# Module_T_H_04vP.net
KiCad netlist of a schematic drawn in EAGLE
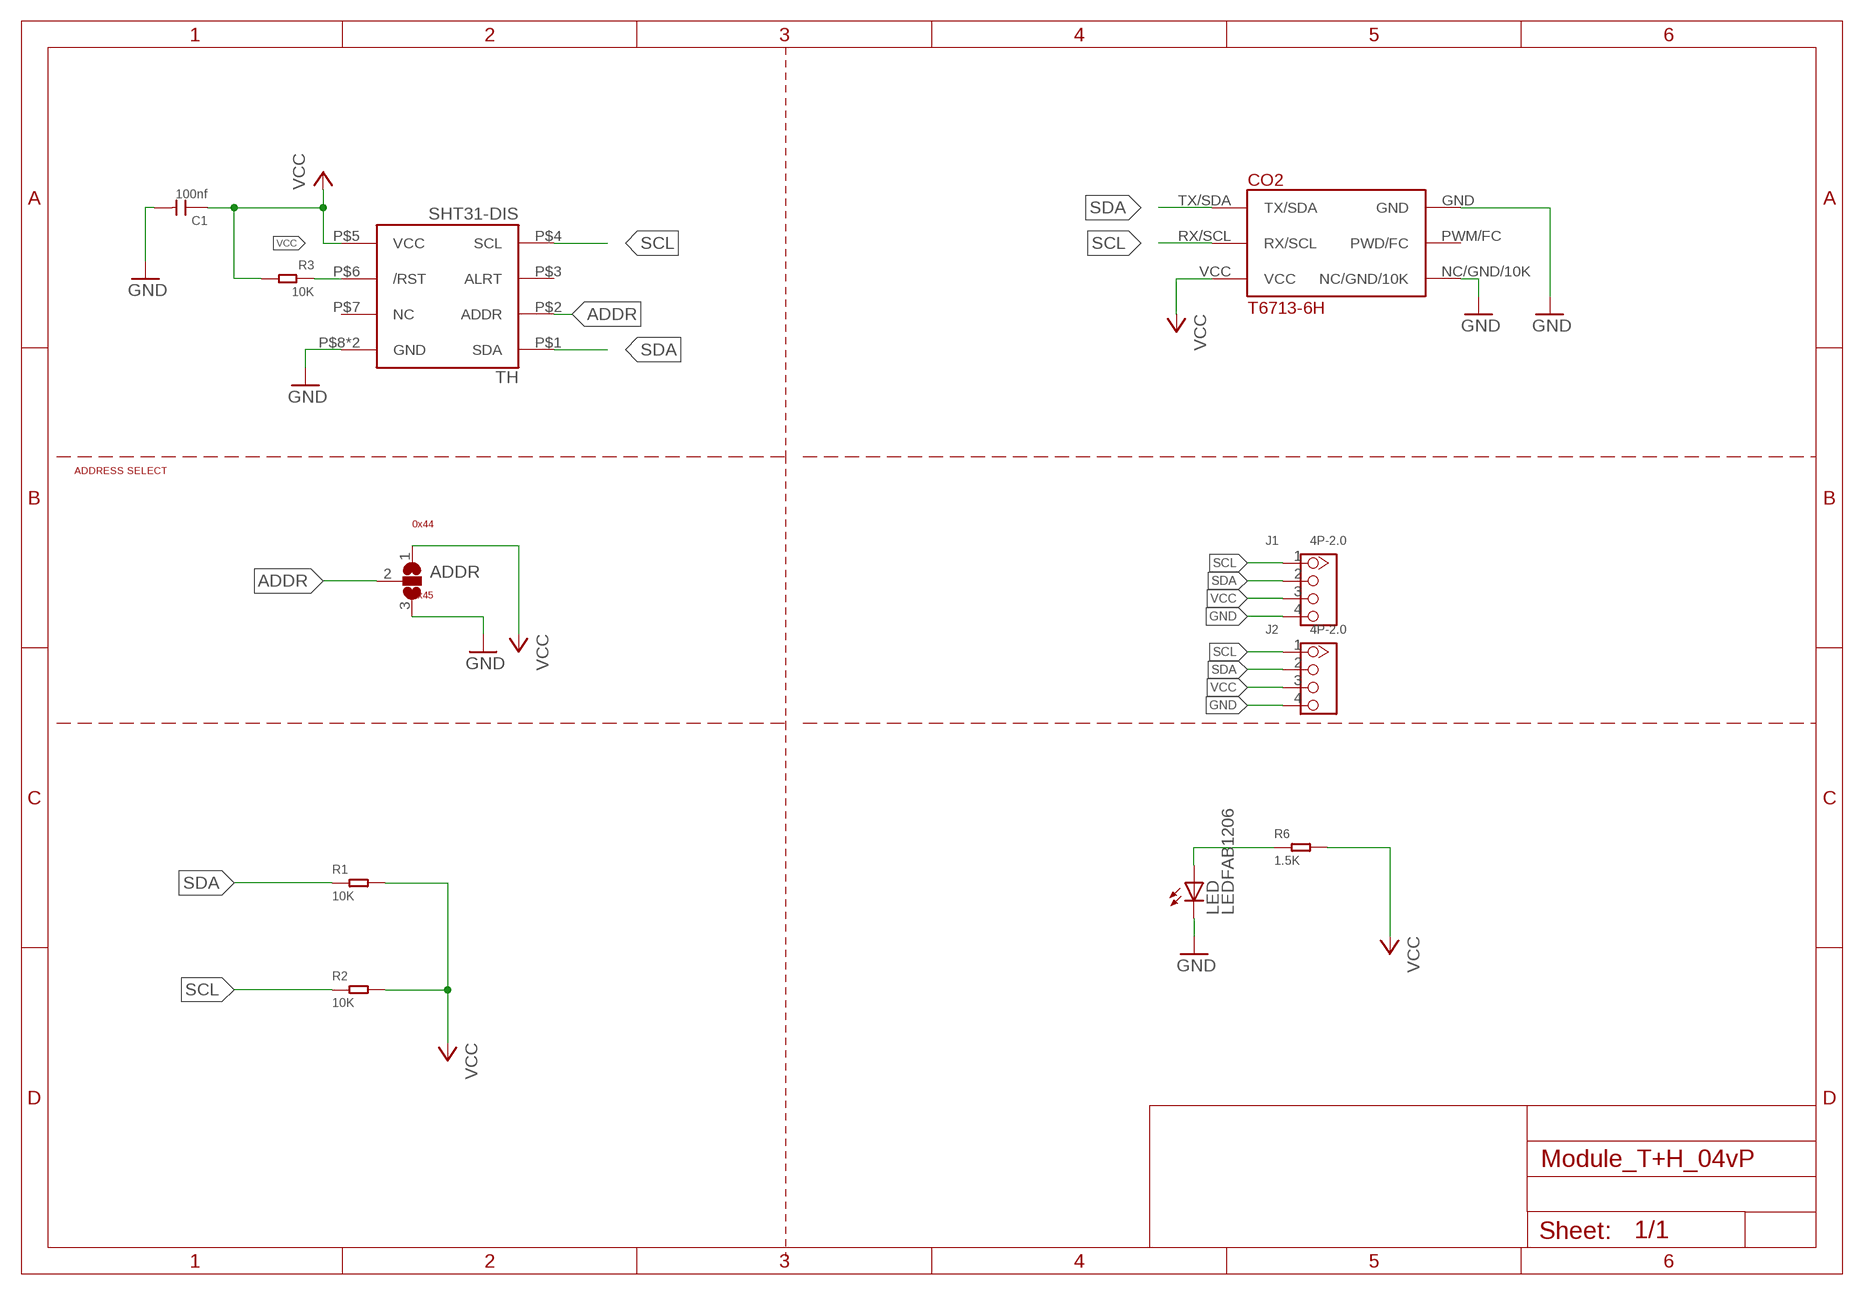
[diagram p0: schematic, sheet 1]

(export (version "E")
  (design (tool "Eeschema 10.0.6"))
  (components
    (comp (ref "ADDR")
      (value "SJ2W")
      (footprint "eagle-import:SJ_2")
      (libsource (lib "eagle-import") (part "SJ2W"))
    )
    (comp (ref "C1")
      (value "100nf")
      (footprint "eagle-import:C0805")
      (fields (field (name "MPN") "CC0805KRX7R9BB104"))
      (libsource (lib "eagle-import") (part "CERAMIC-100NF-50V-10%-X7R(0805)"))
    )
    (comp (ref "CO2")
      (value "T6713-6H")
      (footprint "eagle-import:PINS")
      (libsource (lib "eagle-import") (part "T6713-6H"))
    )
    (comp (ref "J1")
      (value "4P-2.0")
      (footprint "eagle-import:HW4-2.0")
      (libsource (lib "eagle-import") (part "GROVE-CONNECTOR-DIP(4P-2.0)"))
    )
    (comp (ref "J2")
      (value "4P-2.0")
      (footprint "eagle-import:HW4-2.0")
      (libsource (lib "eagle-import") (part "GROVE-CONNECTOR-DIP(4P-2.0)"))
    )
    (comp (ref "LED")
      (value "LEDFAB1206")
      (footprint "eagle-import:LED1206FAB")
      (libsource (lib "eagle-import") (part "LEDFAB1206"))
    )
    (comp (ref "R1")
      (value "10K")
      (footprint "eagle-import:R0805")
      (fields (field (name "MPN") "RC0805FR-0710KL"))
      (libsource (lib "eagle-import") (part "SMD-RES-10K-1%-1/8W(0805)"))
    )
    (comp (ref "R2")
      (value "10K")
      (footprint "eagle-import:R0805")
      (fields (field (name "MPN") "RC0805FR-0710KL"))
      (libsource (lib "eagle-import") (part "SMD-RES-10K-1%-1/8W(0805)"))
    )
    (comp (ref "R3")
      (value "10K")
      (footprint "eagle-import:R0805")
      (fields (field (name "MPN") "RC0805FR-0710KL"))
      (libsource (lib "eagle-import") (part "SMD-RES-10K-1%-1/8W(0805)"))
    )
    (comp (ref "R6")
      (value "1.5K")
      (footprint "eagle-import:R0805")
      (fields (field (name "MPN") "RC0805FR-071K5L"))
      (libsource (lib "eagle-import") (part "SMD-RES-1.5K-1%-1/8W(0805)"))
    )
    (comp (ref "TH")
      (value "SHT31-DIS")
      (footprint "eagle-import:SHT3X")
      (libsource (lib "eagle-import") (part "SHT31-DIS"))
    )
  )
  (nets
    (net (code "1") (name "ADDR") (class "Default")
      (node (ref "ADDR") (pin "2") (pinfunction "2_2") (pintype "passive"))
      (node (ref "TH") (pin "P$2") (pinfunction "ADDR_P$2") (pintype "bidirectional"))
    )
    (net (code "2") (name "GND") (class "Default")
      (node (ref "ADDR") (pin "3") (pinfunction "3_3") (pintype "passive"))
      (node (ref "C1") (pin "2") (pinfunction "2_2") (pintype "passive"))
      (node (ref "CO2") (pin "GND") (pinfunction "GND_GND") (pintype "bidirectional"))
      (node (ref "CO2") (pin "NC/GND/10K") (pinfunction "NC/GND/10K_NC/GND/10K") (pintype "bidirectional"))
      (node (ref "J1") (pin "4") (pinfunction "4_4") (pintype "bidirectional"))
      (node (ref "J2") (pin "4") (pinfunction "4_4") (pintype "bidirectional"))
      (node (ref "LED") (pin "2") (pinfunction "C_2") (pintype "passive"))
      (node (ref "TH") (pin "P$8") (pinfunction "GND_P$8") (pintype "bidirectional"))
      (node (ref "TH") (pin "PAD") (pinfunction "GND_PAD") (pintype "bidirectional"))
    )
    (net (code "3") (name "Net-(LED-A)") (class "Default")
      (node (ref "LED") (pin "1") (pinfunction "A_1") (pintype "passive"))
      (node (ref "R6") (pin "1") (pinfunction "1_1") (pintype "passive"))
    )
    (net (code "4") (name "Net-(TH-{slash}RST)") (class "Default")
      (node (ref "R3") (pin "1") (pinfunction "1_1") (pintype "passive"))
      (node (ref "TH") (pin "P$6") (pinfunction "/RST_P$6") (pintype "bidirectional"))
    )
    (net (code "5") (name "SCL") (class "Default")
      (node (ref "CO2") (pin "RX/SCL") (pinfunction "RX/SCL_RX/SCL") (pintype "bidirectional"))
      (node (ref "J1") (pin "1") (pinfunction "1_1") (pintype "bidirectional"))
      (node (ref "J2") (pin "1") (pinfunction "1_1") (pintype "bidirectional"))
      (node (ref "R2") (pin "1") (pinfunction "1_1") (pintype "passive"))
      (node (ref "TH") (pin "P$4") (pinfunction "SCL_P$4") (pintype "bidirectional"))
    )
    (net (code "6") (name "SDA") (class "Default")
      (node (ref "CO2") (pin "TX/SDA") (pinfunction "TX/SDA_TX/SDA") (pintype "bidirectional"))
      (node (ref "J1") (pin "2") (pinfunction "2_2") (pintype "bidirectional"))
      (node (ref "J2") (pin "2") (pinfunction "2_2") (pintype "bidirectional"))
      (node (ref "R1") (pin "1") (pinfunction "1_1") (pintype "passive"))
      (node (ref "TH") (pin "P$1") (pinfunction "SDA_P$1") (pintype "bidirectional"))
    )
    (net (code "7") (name "VCC") (class "Default")
      (node (ref "ADDR") (pin "1") (pinfunction "1_1") (pintype "passive"))
      (node (ref "C1") (pin "1") (pinfunction "1_1") (pintype "passive"))
      (node (ref "CO2") (pin "VCC") (pinfunction "VCC_VCC") (pintype "bidirectional"))
      (node (ref "J1") (pin "3") (pinfunction "3_3") (pintype "bidirectional"))
      (node (ref "J2") (pin "3") (pinfunction "3_3") (pintype "bidirectional"))
      (node (ref "R1") (pin "2") (pinfunction "2_2") (pintype "passive"))
      (node (ref "R2") (pin "2") (pinfunction "2_2") (pintype "passive"))
      (node (ref "R3") (pin "2") (pinfunction "2_2") (pintype "passive"))
      (node (ref "R6") (pin "2") (pinfunction "2_2") (pintype "passive"))
      (node (ref "TH") (pin "P$5") (pinfunction "VCC_P$5") (pintype "bidirectional"))
    )
    (net (code "8") (name "unconnected-(CO2-PWD{slash}FC-PadPWM{slash}FC)") (class "Default")
      (node (ref "CO2") (pin "PWM/FC") (pinfunction "PWD/FC_PWM/FC") (pintype "bidirectional"))
    )
    (net (code "9") (name "unconnected-(TH-ALRT-PadP$3)") (class "Default")
      (node (ref "TH") (pin "P$3") (pinfunction "ALRT_P$3") (pintype "bidirectional"))
    )
    (net (code "10") (name "unconnected-(TH-NC-PadP$7)") (class "Default")
      (node (ref "TH") (pin "P$7") (pinfunction "NC_P$7") (pintype "bidirectional"))
    )
  )
)
